# Juricic_Napajanje.net
KiCad netlist of a schematic drawn in Altium Designer
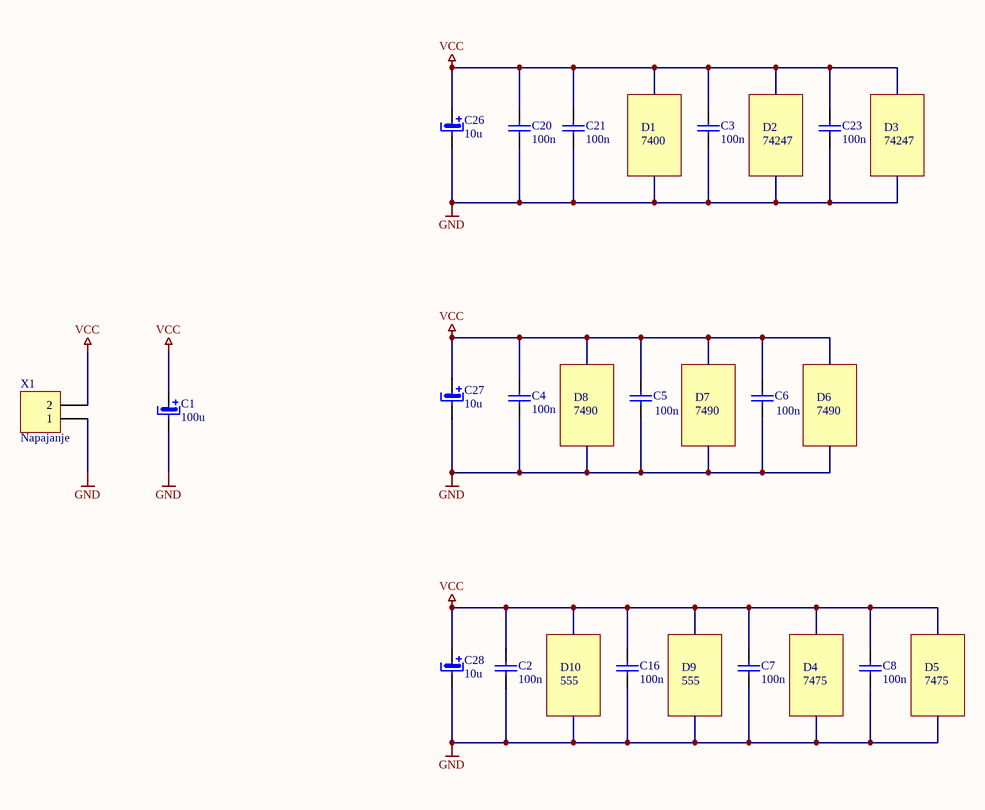
[diagram p0: Juricic_Napajanje.SchDoc]

(export (version "E")
  (design (tool "Eeschema 10.0.6"))
  (components
    (comp (ref "C1")
      (value "100u")
      (footprint "CAPR5-4X5")
      (description "100u capacitor")
      (libsource (lib "Indikator_lib") (part "Elko"))
    )
    (comp (ref "C2")
      (value "100n")
      (footprint "C0805")
      (description "100n capacitor")
      (fields (field (name "PUBLISHER") "Altium Limited"))
      (libsource (lib "Miscellaneous Devices") (part "Cap"))
    )
    (comp (ref "C3")
      (value "100n")
      (footprint "C0805")
      (description "100n capacitor")
      (fields (field (name "PUBLISHER") "Altium Limited"))
      (libsource (lib "Miscellaneous Devices") (part "Cap"))
    )
    (comp (ref "C4")
      (value "100n")
      (footprint "C0805")
      (description "100n capacitor")
      (fields (field (name "PUBLISHER") "Altium Limited"))
      (libsource (lib "Miscellaneous Devices") (part "Cap"))
    )
    (comp (ref "C5")
      (value "100n")
      (footprint "C0805")
      (description "100n capacitor")
      (fields (field (name "PUBLISHER") "Altium Limited"))
      (libsource (lib "Miscellaneous Devices") (part "Cap"))
    )
    (comp (ref "C6")
      (value "100n")
      (footprint "C0805")
      (description "100n capacitor")
      (fields (field (name "PUBLISHER") "Altium Limited"))
      (libsource (lib "Miscellaneous Devices") (part "Cap"))
    )
    (comp (ref "C7")
      (value "100n")
      (footprint "C0805")
      (description "100n capacitor")
      (fields (field (name "PUBLISHER") "Altium Limited"))
      (libsource (lib "Miscellaneous Devices") (part "Cap"))
    )
    (comp (ref "C8")
      (value "100n")
      (footprint "C0805")
      (description "100n capacitor")
      (fields (field (name "PUBLISHER") "Altium Limited"))
      (libsource (lib "Miscellaneous Devices") (part "Cap"))
    )
    (comp (ref "C16")
      (value "100n")
      (footprint "C0805")
      (description "100n capacitor")
      (fields (field (name "PUBLISHER") "Altium Limited"))
      (libsource (lib "Miscellaneous Devices") (part "Cap"))
    )
    (comp (ref "C20")
      (value "100n")
      (footprint "C0805")
      (description "100n capacitor")
      (fields (field (name "PUBLISHER") "Altium Limited"))
      (libsource (lib "Miscellaneous Devices") (part "Cap"))
    )
    (comp (ref "C21")
      (value "100n")
      (footprint "C0805")
      (description "100n capacitor")
      (fields (field (name "PUBLISHER") "Altium Limited"))
      (libsource (lib "Miscellaneous Devices") (part "Cap"))
    )
    (comp (ref "C23")
      (value "100n")
      (footprint "C0805")
      (description "100n capacitor")
      (fields (field (name "PUBLISHER") "Altium Limited"))
      (libsource (lib "Miscellaneous Devices") (part "Cap"))
    )
    (comp (ref "C26")
      (value "10u")
      (footprint "CAPR5-4X5")
      (description "10u capacitor")
      (libsource (lib "Indikator_lib") (part "Elko"))
    )
    (comp (ref "C27")
      (value "10u")
      (footprint "CAPR5-4X5")
      (description "10u capacitor")
      (libsource (lib "Indikator_lib") (part "Elko"))
    )
    (comp (ref "C28")
      (value "10u")
      (footprint "CAPR5-4X5")
      (description "10u capacitor")
      (libsource (lib "Indikator_lib") (part "Elko"))
    )
    (comp (ref "X1")
      (value "Napajanje")
      (footprint "HDR1X2")
      (description "Header, 2-Pin")
      (fields (field (name "PUBLISHER") "Altium Limited"))
      (libsource (lib "Miscellaneous Connectors") (part "Header 2"))
    )
  )
  (nets
    (net (code "1") (name "GND") (class "Default")
      (node (ref "C1") (pin "2") (pintype "passive"))
      (node (ref "C16") (pin "1") (pinfunction "1_1") (pintype "passive"))
      (node (ref "C2") (pin "1") (pinfunction "1_1") (pintype "passive"))
      (node (ref "C20") (pin "1") (pinfunction "1_1") (pintype "passive"))
      (node (ref "C21") (pin "1") (pinfunction "1_1") (pintype "passive"))
      (node (ref "C23") (pin "1") (pinfunction "1_1") (pintype "passive"))
      (node (ref "C26") (pin "2") (pintype "passive"))
      (node (ref "C27") (pin "2") (pintype "passive"))
      (node (ref "C28") (pin "2") (pintype "passive"))
      (node (ref "C3") (pin "1") (pinfunction "1_1") (pintype "passive"))
      (node (ref "C4") (pin "1") (pinfunction "1_1") (pintype "passive"))
      (node (ref "C5") (pin "1") (pinfunction "1_1") (pintype "passive"))
      (node (ref "C6") (pin "1") (pinfunction "1_1") (pintype "passive"))
      (node (ref "C7") (pin "1") (pinfunction "1_1") (pintype "passive"))
      (node (ref "C8") (pin "1") (pinfunction "1_1") (pintype "passive"))
      (node (ref "X1") (pin "1") (pinfunction "1_1") (pintype "passive"))
    )
    (net (code "2") (name "VCC") (class "Default")
      (node (ref "C1") (pin "1") (pinfunction "16_1") (pintype "passive"))
      (node (ref "C16") (pin "2") (pinfunction "2_2") (pintype "passive"))
      (node (ref "C2") (pin "2") (pinfunction "2_2") (pintype "passive"))
      (node (ref "C20") (pin "2") (pinfunction "2_2") (pintype "passive"))
      (node (ref "C21") (pin "2") (pinfunction "2_2") (pintype "passive"))
      (node (ref "C23") (pin "2") (pinfunction "2_2") (pintype "passive"))
      (node (ref "C26") (pin "1") (pinfunction "16_1") (pintype "passive"))
      (node (ref "C27") (pin "1") (pinfunction "16_1") (pintype "passive"))
      (node (ref "C28") (pin "1") (pinfunction "16_1") (pintype "passive"))
      (node (ref "C3") (pin "2") (pinfunction "2_2") (pintype "passive"))
      (node (ref "C4") (pin "2") (pinfunction "2_2") (pintype "passive"))
      (node (ref "C5") (pin "2") (pinfunction "2_2") (pintype "passive"))
      (node (ref "C6") (pin "2") (pinfunction "2_2") (pintype "passive"))
      (node (ref "C7") (pin "2") (pinfunction "2_2") (pintype "passive"))
      (node (ref "C8") (pin "2") (pinfunction "2_2") (pintype "passive"))
      (node (ref "X1") (pin "2") (pinfunction "2_2") (pintype "passive"))
    )
  )
)
